# watch.net
KiCad netlist of a schematic drawn in EAGLE
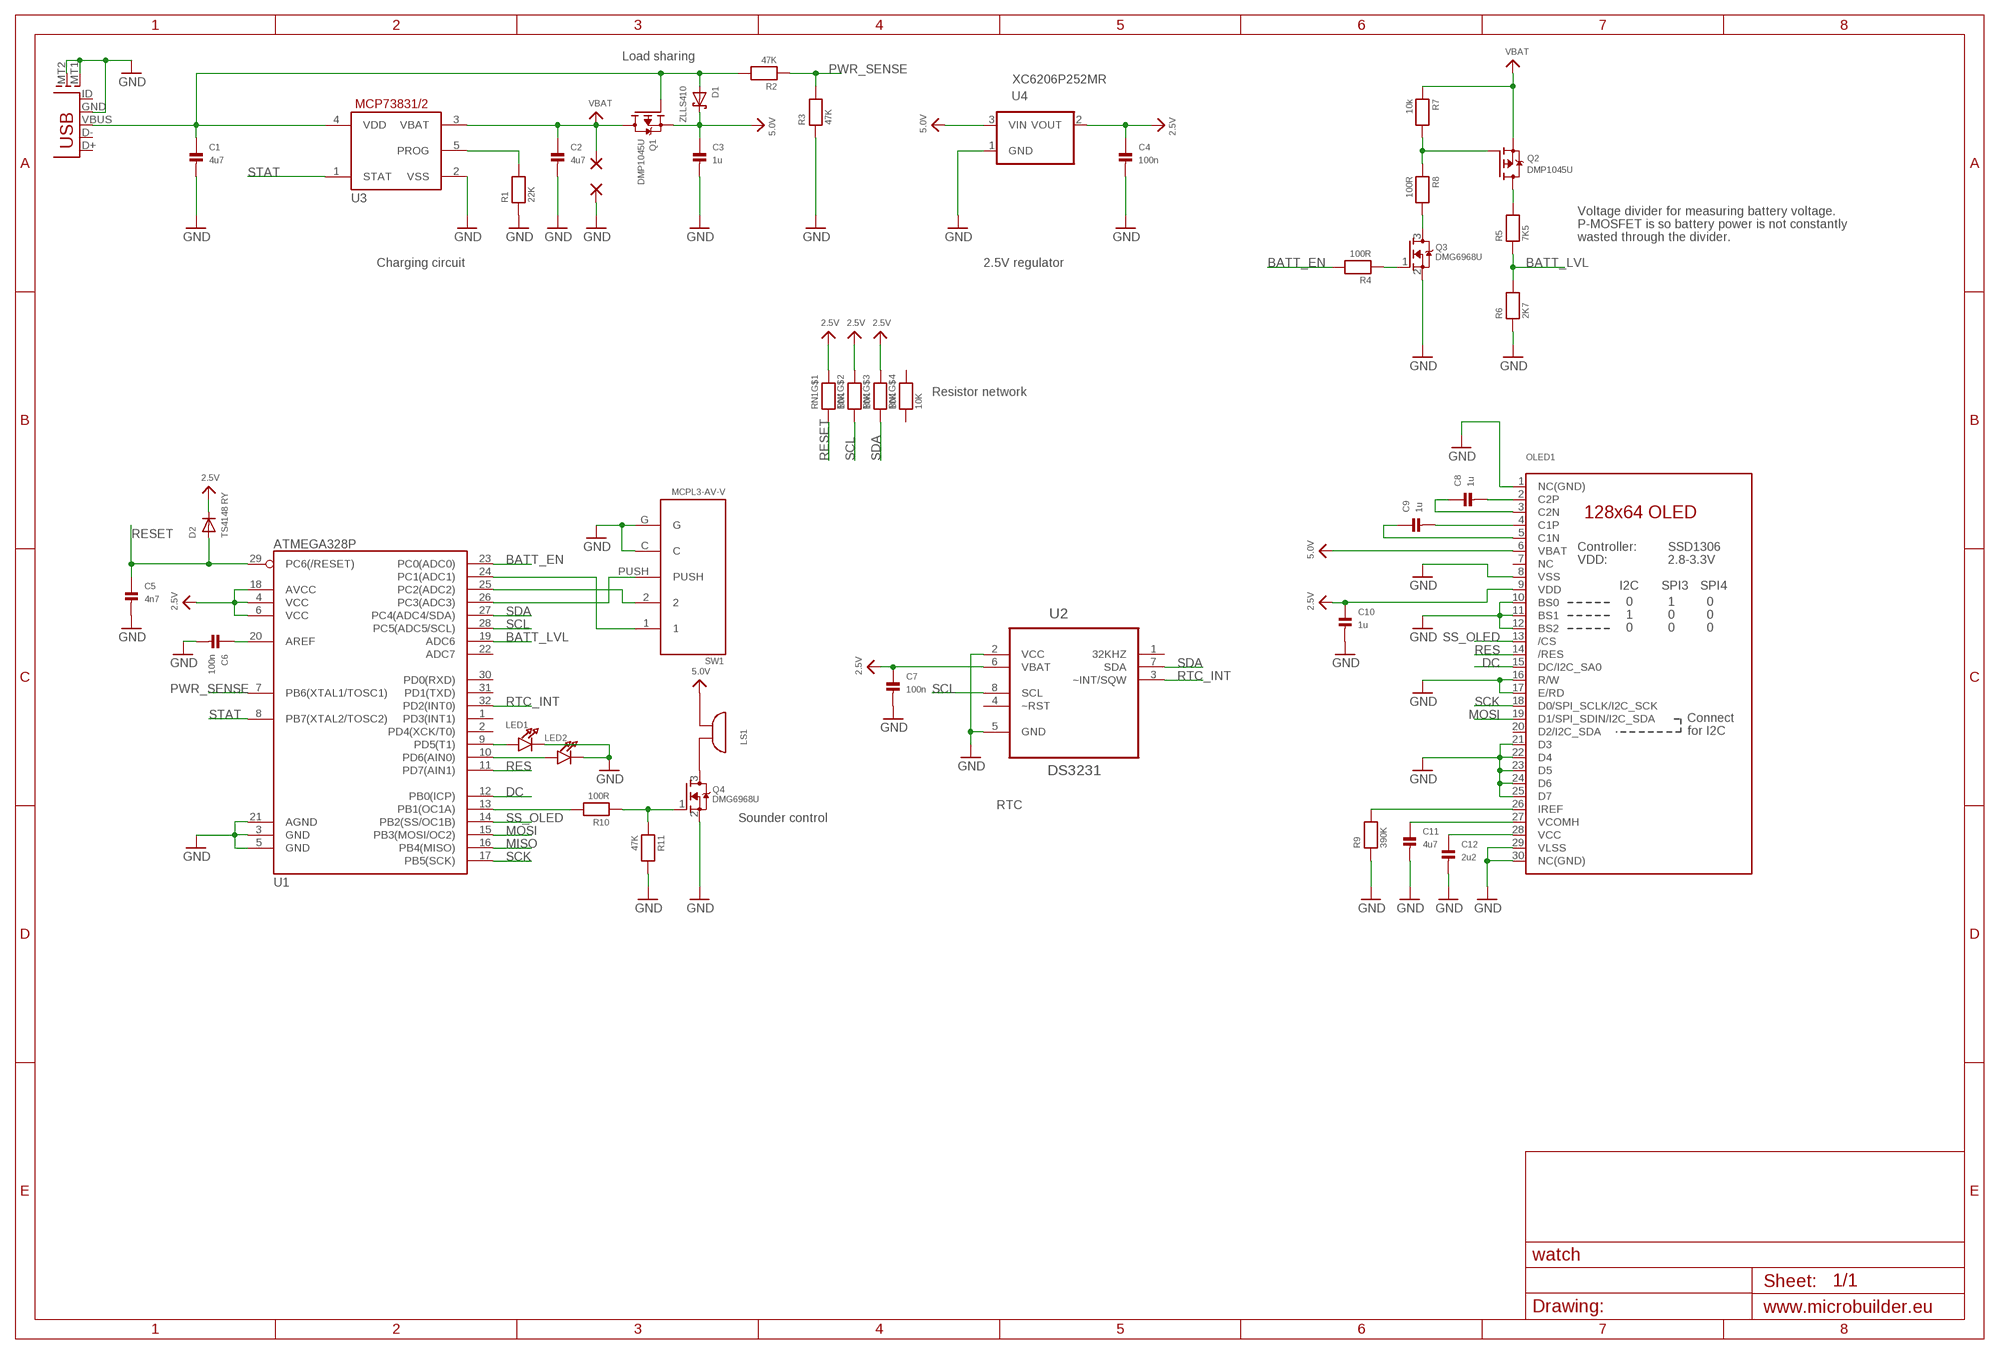
[diagram p0: schematic, sheet 1]

(export (version "E")
  (design (tool "Eeschema 10.0.6"))
  (components
    (comp (ref "C1")
      (value "4u7")
      (footprint "eagle-import:0805")
      (libsource (lib "eagle-import") (part "CAP_CERAMIC0805"))
    )
    (comp (ref "C2")
      (value "4u7")
      (footprint "eagle-import:0805")
      (libsource (lib "eagle-import") (part "CAP_CERAMIC0805"))
    )
    (comp (ref "C3")
      (value "1u")
      (footprint "eagle-import:0805")
      (libsource (lib "eagle-import") (part "CAP_CERAMIC0805"))
    )
    (comp (ref "C4")
      (value "100n")
      (footprint "eagle-import:0805")
      (libsource (lib "eagle-import") (part "CAP_CERAMIC0805"))
    )
    (comp (ref "C5")
      (value "4n7")
      (footprint "eagle-import:0805")
      (libsource (lib "eagle-import") (part "CAP_CERAMIC0805"))
    )
    (comp (ref "C6")
      (value "100n")
      (footprint "eagle-import:0805")
      (libsource (lib "eagle-import") (part "CAP_CERAMIC0805"))
    )
    (comp (ref "C7")
      (value "100n")
      (footprint "eagle-import:0805")
      (libsource (lib "eagle-import") (part "CAP_CERAMIC0805"))
    )
    (comp (ref "C8")
      (value "1u")
      (footprint "eagle-import:0805")
      (libsource (lib "eagle-import") (part "CAP_CERAMIC0805"))
    )
    (comp (ref "C9")
      (value "1u")
      (footprint "eagle-import:0805")
      (libsource (lib "eagle-import") (part "CAP_CERAMIC0805"))
    )
    (comp (ref "C10")
      (value "1u")
      (footprint "eagle-import:0805")
      (libsource (lib "eagle-import") (part "CAP_CERAMIC0805"))
    )
    (comp (ref "C11")
      (value "4u7")
      (footprint "eagle-import:0805")
      (libsource (lib "eagle-import") (part "CAP_CERAMIC0805"))
    )
    (comp (ref "C12")
      (value "2u2")
      (footprint "eagle-import:0805")
      (libsource (lib "eagle-import") (part "CAP_CERAMIC0805"))
    )
    (comp (ref "D1")
      (value "ZLLS410")
      (footprint "eagle-import:SOD-323")
      (libsource (lib "eagle-import") (part "DIODE-SCHOTTKYSOD-323"))
    )
    (comp (ref "D2")
      (value "TS4148 RY")
      (footprint "eagle-import:DIODE0805")
      (libsource (lib "eagle-import") (part "DIODE0805"))
    )
    (comp (ref "LED1")
      (value "LED0805")
      (footprint "eagle-import:CHIPLED_0805")
      (libsource (lib "eagle-import") (part "LED0805"))
    )
    (comp (ref "LED2")
      (value "LED0805")
      (footprint "eagle-import:CHIPLED_0805")
      (libsource (lib "eagle-import") (part "LED0805"))
    )
    (comp (ref "LS1")
      (value "ABMT-801-RC")
      (footprint "eagle-import:PIEZO")
      (libsource (lib "eagle-import") (part "ABMT-801-RC"))
    )
    (comp (ref "OLED1")
      (value "DISP_OLED_UG-2864HSWEG01_NOOUTLINE")
      (footprint "eagle-import:UG-2864HSWEG01_1.3_WRAPAROUND")
      (libsource (lib "eagle-import") (part "DISP_OLED_UG-2864HSWEG01_NOOUTLINE"))
    )
    (comp (ref "PAD1")
      (value "SMD2")
      (footprint "eagle-import:SMD1,27-2,54")
      (libsource (lib "eagle-import") (part "SMD2"))
    )
    (comp (ref "PAD2")
      (value "SMD2")
      (footprint "eagle-import:SMD1,27-2,54")
      (libsource (lib "eagle-import") (part "SMD2"))
    )
    (comp (ref "Q1")
      (value "DMP1045U")
      (footprint "eagle-import:SOT23-WIDE")
      (libsource (lib "eagle-import") (part "MOSFET-PWIDE"))
    )
    (comp (ref "Q2")
      (value "DMP1045U")
      (footprint "eagle-import:SOT23-WIDE")
      (libsource (lib "eagle-import") (part "MOSFET-PWIDE"))
    )
    (comp (ref "Q3")
      (value "DMG6968U")
      (footprint "eagle-import:SOT23-WIDE")
      (libsource (lib "eagle-import") (part "MOSFET-NWIDE"))
    )
    (comp (ref "Q4")
      (value "DMG6968U")
      (footprint "eagle-import:SOT23-WIDE")
      (libsource (lib "eagle-import") (part "MOSFET-NWIDE"))
    )
    (comp (ref "R1")
      (value "22K")
      (footprint "eagle-import:0805")
      (libsource (lib "eagle-import") (part "RESISTOR0805"))
    )
    (comp (ref "R2")
      (value "47K")
      (footprint "eagle-import:0805_NOTHERMALS")
      (libsource (lib "eagle-import") (part "RESISTOR0805_NOTHERMALS"))
    )
    (comp (ref "R3")
      (value "47K")
      (footprint "eagle-import:0805_NOTHERMALS")
      (libsource (lib "eagle-import") (part "RESISTOR0805_NOTHERMALS"))
    )
    (comp (ref "R4")
      (value "100R")
      (footprint "eagle-import:0805")
      (libsource (lib "eagle-import") (part "RESISTOR0805"))
    )
    (comp (ref "R5")
      (value "7K5")
      (footprint "eagle-import:0805")
      (libsource (lib "eagle-import") (part "RESISTOR0805"))
    )
    (comp (ref "R6")
      (value "2K7")
      (footprint "eagle-import:0805")
      (libsource (lib "eagle-import") (part "RESISTOR0805"))
    )
    (comp (ref "R7")
      (value "10k")
      (footprint "eagle-import:0805")
      (libsource (lib "eagle-import") (part "RESISTOR0805"))
    )
    (comp (ref "R8")
      (value "100R")
      (footprint "eagle-import:0805")
      (libsource (lib "eagle-import") (part "RESISTOR0805"))
    )
    (comp (ref "R9")
      (value "390K")
      (footprint "eagle-import:0805")
      (libsource (lib "eagle-import") (part "RESISTOR0805"))
    )
    (comp (ref "R10")
      (value "100R")
      (footprint "eagle-import:0805")
      (libsource (lib "eagle-import") (part "RESISTOR0805"))
    )
    (comp (ref "R11")
      (value "47K")
      (footprint "eagle-import:0805")
      (libsource (lib "eagle-import") (part "RESISTOR0805"))
    )
    (comp (ref "RN1")
      (value "10K")
      (footprint "eagle-import:RESPACK_4X0603")
      (libsource (lib "eagle-import") (part "RESISTOR_4PACK"))
    )
    (comp (ref "SW1")
      (value "MCPL3-AV-V")
      (footprint "eagle-import:MCPL3-AC-V")
      (libsource (lib "eagle-import") (part "MCPL3-AV-V"))
    )
    (comp (ref "U1")
      (value "ATMEGA328P")
      (footprint "eagle-import:TQFP32-08")
      (libsource (lib "eagle-import") (part "ATMEGA328_SMT"))
    )
    (comp (ref "U2")
      (value "DS3231")
      (footprint "eagle-import:SOIC8_150MIL")
      (libsource (lib "eagle-import") (part "DS3231MZ+"))
    )
    (comp (ref "U3")
      (value "MCP73832T-2ACI/OT")
      (footprint "eagle-import:SOT23-5L")
      (libsource (lib "eagle-import") (part "MCP73831/OT"))
    )
    (comp (ref "U4")
      (value "XC6206P252MR")
      (footprint "eagle-import:SOT-23")
      (libsource (lib "eagle-import") (part "MCP1700T-2502E/TTWIDE_PAD"))
    )
    (comp (ref "USB1")
      (value "USB-MICROBLARGEPAD")
      (footprint "eagle-import:USB-MICROB_LARGEPAD")
      (libsource (lib "eagle-import") (part "USB-MICROBLARGEPAD"))
    )
  )
  (nets
    (net (code "1") (name "/BATT_EN") (class "Default")
      (node (ref "R4") (pin "2") (pinfunction "2_2") (pintype "passive"))
      (node (ref "U1") (pin "23") (pinfunction "PC0(ADC0)_23") (pintype "bidirectional"))
    )
    (net (code "2") (name "/BATT_LVL") (class "Default")
      (node (ref "R5") (pin "1") (pinfunction "1_1") (pintype "passive"))
      (node (ref "R6") (pin "2") (pinfunction "2_2") (pintype "passive"))
      (node (ref "U1") (pin "19") (pinfunction "ADC6_19") (pintype "bidirectional"))
    )
    (net (code "3") (name "/DC") (class "Default")
      (node (ref "OLED1") (pin "15") (pinfunction "DC/I2C_SA0_15") (pintype "input"))
      (node (ref "U1") (pin "12") (pinfunction "PB0(ICP)_12") (pintype "bidirectional"))
    )
    (net (code "4") (name "/MISO") (class "Default")
      (node (ref "U1") (pin "16") (pinfunction "PB4(MISO)_16") (pintype "bidirectional"))
    )
    (net (code "5") (name "/MOSI") (class "Default")
      (node (ref "OLED1") (pin "19") (pinfunction "D1/SPI_SDIN/I2C_SDA_19") (pintype "bidirectional"))
      (node (ref "U1") (pin "15") (pinfunction "PB3(MOSI/OC2)_15") (pintype "bidirectional"))
    )
    (net (code "6") (name "/PWR_SENSE") (class "Default")
      (node (ref "R2") (pin "1") (pinfunction "1_1") (pintype "passive"))
      (node (ref "R3") (pin "2") (pinfunction "2_2") (pintype "passive"))
      (node (ref "U1") (pin "7") (pinfunction "PB6(XTAL1/TOSC1)_7") (pintype "bidirectional"))
    )
    (net (code "7") (name "/RES") (class "Default")
      (node (ref "OLED1") (pin "14") (pinfunction "/RES_14") (pintype "input"))
      (node (ref "U1") (pin "11") (pinfunction "PD7(AIN1)_11") (pintype "bidirectional"))
    )
    (net (code "8") (name "/RESET") (class "Default")
      (node (ref "C5") (pin "1") (pinfunction "P$1_1") (pintype "passive"))
      (node (ref "D2") (pin "1") (pinfunction "A_1") (pintype "passive"))
      (node (ref "RN1") (pin "1") (pinfunction "1_1") (pintype "passive"))
      (node (ref "U1") (pin "29") (pinfunction "PC6(/RESET)_29") (pintype "bidirectional"))
    )
    (net (code "9") (name "/RTC_INT") (class "Default")
      (node (ref "U1") (pin "32") (pinfunction "PD2(INT0)_32") (pintype "bidirectional"))
      (node (ref "U2") (pin "3") (pinfunction "~{INT/SQW}_3") (pintype "output"))
    )
    (net (code "10") (name "/SCK") (class "Default")
      (node (ref "OLED1") (pin "18") (pinfunction "D0/SPI_SCLK/I2C_SCK_18") (pintype "bidirectional"))
      (node (ref "U1") (pin "17") (pinfunction "PB5(SCK)_17") (pintype "bidirectional"))
    )
    (net (code "11") (name "/SCL") (class "Default")
      (node (ref "RN1") (pin "2") (pinfunction "1_2") (pintype "passive"))
      (node (ref "U1") (pin "28") (pinfunction "PC5(ADC5/SCL)_28") (pintype "bidirectional"))
      (node (ref "U2") (pin "8") (pinfunction "SCL_8") (pintype "input"))
    )
    (net (code "12") (name "/SDA") (class "Default")
      (node (ref "RN1") (pin "3") (pinfunction "1_3") (pintype "passive"))
      (node (ref "U1") (pin "27") (pinfunction "PC4(ADC4/SDA)_27") (pintype "bidirectional"))
      (node (ref "U2") (pin "7") (pinfunction "SDA_7") (pintype "bidirectional"))
    )
    (net (code "13") (name "/SS_OLED") (class "Default")
      (node (ref "OLED1") (pin "13") (pinfunction "/CS_13") (pintype "input"))
      (node (ref "U1") (pin "14") (pinfunction "PB2(SS/OC1B)_14") (pintype "bidirectional"))
    )
    (net (code "14") (name "/STAT") (class "Default")
      (node (ref "U1") (pin "8") (pinfunction "PB7(XTAL2/TOSC2)_8") (pintype "bidirectional"))
      (node (ref "U3") (pin "1") (pinfunction "STAT_1") (pintype "output"))
    )
    (net (code "15") (name "2.5V") (class "Default")
      (node (ref "C10") (pin "1") (pinfunction "P$1_1") (pintype "passive"))
      (node (ref "C4") (pin "1") (pinfunction "P$1_1") (pintype "passive"))
      (node (ref "C7") (pin "1") (pinfunction "P$1_1") (pintype "passive"))
      (node (ref "D2") (pin "2") (pinfunction "C_2") (pintype "passive"))
      (node (ref "OLED1") (pin "9") (pinfunction "VDD_9") (pintype "power_in"))
      (node (ref "RN1") (pin "6") (pinfunction "2_6") (pintype "passive"))
      (node (ref "RN1") (pin "7") (pinfunction "2_7") (pintype "passive"))
      (node (ref "RN1") (pin "8") (pinfunction "2_8") (pintype "passive"))
      (node (ref "U1") (pin "18") (pinfunction "AVCC_18") (pintype "bidirectional"))
      (node (ref "U1") (pin "4") (pinfunction "VCC_4") (pintype "bidirectional"))
      (node (ref "U1") (pin "6") (pinfunction "VCC_6") (pintype "bidirectional"))
      (node (ref "U2") (pin "6") (pinfunction "VBAT_6") (pintype "power_in"))
      (node (ref "U4") (pin "2") (pinfunction "VOUT_2") (pintype "output"))
    )
    (net (code "16") (name "5.0V") (class "Default")
      (node (ref "C3") (pin "1") (pinfunction "P$1_1") (pintype "passive"))
      (node (ref "D1") (pin "C") (pinfunction "C_C") (pintype "passive"))
      (node (ref "LS1") (pin "1") (pinfunction "VCC_1") (pintype "passive"))
      (node (ref "OLED1") (pin "6") (pinfunction "VBAT_6") (pintype "input"))
      (node (ref "Q1") (pin "2") (pinfunction "S_2") (pintype "passive"))
      (node (ref "U4") (pin "3") (pinfunction "VIN_3") (pintype "power_in"))
    )
    (net (code "17") (name "GND") (class "Default")
      (node (ref "C1") (pin "2") (pinfunction "P$2_2") (pintype "passive"))
      (node (ref "C10") (pin "2") (pinfunction "P$2_2") (pintype "passive"))
      (node (ref "C11") (pin "2") (pinfunction "P$2_2") (pintype "passive"))
      (node (ref "C12") (pin "2") (pinfunction "P$2_2") (pintype "passive"))
      (node (ref "C2") (pin "2") (pinfunction "P$2_2") (pintype "passive"))
      (node (ref "C3") (pin "2") (pinfunction "P$2_2") (pintype "passive"))
      (node (ref "C4") (pin "2") (pinfunction "P$2_2") (pintype "passive"))
      (node (ref "C5") (pin "2") (pinfunction "P$2_2") (pintype "passive"))
      (node (ref "C6") (pin "2") (pinfunction "P$2_2") (pintype "passive"))
      (node (ref "C7") (pin "2") (pinfunction "P$2_2") (pintype "passive"))
      (node (ref "LED1") (pin "C") (pinfunction "C_C") (pintype "passive"))
      (node (ref "LED2") (pin "C") (pinfunction "C_C") (pintype "passive"))
      (node (ref "OLED1") (pin "1") (pinfunction "NC(GND)_1") (pintype "input"))
      (node (ref "OLED1") (pin "10") (pinfunction "BS0_10") (pintype "input"))
      (node (ref "OLED1") (pin "11") (pinfunction "BS1_11") (pintype "input"))
      (node (ref "OLED1") (pin "12") (pinfunction "BS2_12") (pintype "input"))
      (node (ref "OLED1") (pin "16") (pinfunction "R/W_16") (pintype "input"))
      (node (ref "OLED1") (pin "17") (pinfunction "E/RD_17") (pintype "input"))
      (node (ref "OLED1") (pin "21") (pinfunction "D3_21") (pintype "bidirectional"))
      (node (ref "OLED1") (pin "22") (pinfunction "D4_22") (pintype "bidirectional"))
      (node (ref "OLED1") (pin "23") (pinfunction "D5_23") (pintype "bidirectional"))
      (node (ref "OLED1") (pin "24") (pinfunction "D6_24") (pintype "bidirectional"))
      (node (ref "OLED1") (pin "25") (pinfunction "D7_25") (pintype "bidirectional"))
      (node (ref "OLED1") (pin "29") (pinfunction "VLSS_29") (pintype "power_in"))
      (node (ref "OLED1") (pin "30") (pinfunction "NC(GND)_30") (pintype "input"))
      (node (ref "OLED1") (pin "8") (pinfunction "VSS_8") (pintype "power_in"))
      (node (ref "PAD2") (pin "1") (pinfunction "P_1") (pintype "passive"))
      (node (ref "Q3") (pin "2") (pinfunction "S_2") (pintype "bidirectional"))
      (node (ref "Q4") (pin "2") (pinfunction "S_2") (pintype "bidirectional"))
      (node (ref "R1") (pin "1") (pinfunction "1_1") (pintype "passive"))
      (node (ref "R11") (pin "2") (pinfunction "2_2") (pintype "passive"))
      (node (ref "R3") (pin "1") (pinfunction "1_1") (pintype "passive"))
      (node (ref "R6") (pin "1") (pinfunction "1_1") (pintype "passive"))
      (node (ref "R9") (pin "1") (pinfunction "1_1") (pintype "passive"))
      (node (ref "SW1") (pin "C") (pinfunction "C_C") (pintype "bidirectional"))
      (node (ref "SW1") (pin "G") (pinfunction "G_G") (pintype "bidirectional"))
      (node (ref "U1") (pin "21") (pinfunction "AGND_21") (pintype "bidirectional"))
      (node (ref "U1") (pin "3") (pinfunction "GND_3") (pintype "bidirectional"))
      (node (ref "U1") (pin "5") (pinfunction "GND_5") (pintype "bidirectional"))
      (node (ref "U2") (pin "2") (pinfunction "VCC_2") (pintype "power_in"))
      (node (ref "U2") (pin "5") (pinfunction "GND_5") (pintype "passive"))
      (node (ref "U3") (pin "2") (pinfunction "VSS_2") (pintype "power_in"))
      (node (ref "U4") (pin "1") (pinfunction "GND_1") (pintype "passive"))
      (node (ref "USB1") (pin "GND") (pinfunction "GND_GND") (pintype "bidirectional"))
      (node (ref "USB1") (pin "MT1") (pinfunction "SHEILD1_MT1") (pintype "bidirectional"))
      (node (ref "USB1") (pin "MT2") (pinfunction "SHEILD2_MT2") (pintype "bidirectional"))
    )
    (net (code "18") (name "Net-(C1-P$1)") (class "Default")
      (node (ref "C1") (pin "1") (pinfunction "P$1_1") (pintype "passive"))
      (node (ref "D1") (pin "A") (pinfunction "A_A") (pintype "passive"))
      (node (ref "Q1") (pin "1") (pinfunction "G_1") (pintype "passive"))
      (node (ref "R2") (pin "2") (pinfunction "2_2") (pintype "passive"))
      (node (ref "U3") (pin "4") (pinfunction "VDD_4") (pintype "power_in"))
      (node (ref "USB1") (pin "VBUS") (pinfunction "VBUS_VBUS") (pintype "bidirectional"))
    )
    (net (code "19") (name "Net-(C6-P$1)") (class "Default")
      (node (ref "C6") (pin "1") (pinfunction "P$1_1") (pintype "passive"))
      (node (ref "U1") (pin "20") (pinfunction "AREF_20") (pintype "bidirectional"))
    )
    (net (code "20") (name "Net-(C8-P$1)") (class "Default")
      (node (ref "C8") (pin "1") (pinfunction "P$1_1") (pintype "passive"))
      (node (ref "OLED1") (pin "3") (pinfunction "C2N_3") (pintype "input"))
    )
    (net (code "21") (name "Net-(C8-P$2)") (class "Default")
      (node (ref "C8") (pin "2") (pinfunction "P$2_2") (pintype "passive"))
      (node (ref "OLED1") (pin "2") (pinfunction "C2P_2") (pintype "input"))
    )
    (net (code "22") (name "Net-(C9-P$1)") (class "Default")
      (node (ref "C9") (pin "1") (pinfunction "P$1_1") (pintype "passive"))
      (node (ref "OLED1") (pin "5") (pinfunction "C1N_5") (pintype "input"))
    )
    (net (code "23") (name "Net-(C9-P$2)") (class "Default")
      (node (ref "C9") (pin "2") (pinfunction "P$2_2") (pintype "passive"))
      (node (ref "OLED1") (pin "4") (pinfunction "C1P_4") (pintype "input"))
    )
    (net (code "24") (name "Net-(C11-P$1)") (class "Default")
      (node (ref "C11") (pin "1") (pinfunction "P$1_1") (pintype "passive"))
      (node (ref "OLED1") (pin "27") (pinfunction "VCOMH_27") (pintype "output"))
    )
    (net (code "25") (name "Net-(C12-P$1)") (class "Default")
      (node (ref "C12") (pin "1") (pinfunction "P$1_1") (pintype "passive"))
      (node (ref "OLED1") (pin "28") (pinfunction "VCC_28") (pintype "power_in"))
    )
    (net (code "26") (name "Net-(LS1-GND)") (class "Default")
      (node (ref "LS1") (pin "2") (pinfunction "GND_2") (pintype "passive"))
      (node (ref "Q4") (pin "3") (pinfunction "D_3") (pintype "bidirectional"))
    )
    (net (code "27") (name "Net-(OLED1-IREF)") (class "Default")
      (node (ref "OLED1") (pin "26") (pinfunction "IREF_26") (pintype "input"))
      (node (ref "R9") (pin "2") (pinfunction "2_2") (pintype "passive"))
    )
    (net (code "28") (name "Net-(Q2-D)") (class "Default")
      (node (ref "Q2") (pin "3") (pinfunction "D_3") (pintype "passive"))
      (node (ref "R5") (pin "2") (pinfunction "2_2") (pintype "passive"))
    )
    (net (code "29") (name "Net-(Q2-G)") (class "Default")
      (node (ref "Q2") (pin "1") (pinfunction "G_1") (pintype "passive"))
      (node (ref "R7") (pin "2") (pinfunction "2_2") (pintype "passive"))
      (node (ref "R8") (pin "1") (pinfunction "1_1") (pintype "passive"))
    )
    (net (code "30") (name "Net-(Q3-D)") (class "Default")
      (node (ref "Q3") (pin "3") (pinfunction "D_3") (pintype "bidirectional"))
      (node (ref "R8") (pin "2") (pinfunction "2_2") (pintype "passive"))
    )
    (net (code "31") (name "Net-(Q3-G)") (class "Default")
      (node (ref "Q3") (pin "1") (pinfunction "G_1") (pintype "bidirectional"))
      (node (ref "R4") (pin "1") (pinfunction "1_1") (pintype "passive"))
    )
    (net (code "32") (name "Net-(Q4-G)") (class "Default")
      (node (ref "Q4") (pin "1") (pinfunction "G_1") (pintype "bidirectional"))
      (node (ref "R10") (pin "1") (pinfunction "1_1") (pintype "passive"))
      (node (ref "R11") (pin "1") (pinfunction "1_1") (pintype "passive"))
    )
    (net (code "33") (name "Net-(U1-PB1(OC1A))") (class "Default")
      (node (ref "R10") (pin "2") (pinfunction "2_2") (pintype "passive"))
      (node (ref "U1") (pin "13") (pinfunction "PB1(OC1A)_13") (pintype "bidirectional"))
    )
    (net (code "34") (name "Net-(U1-PC1(ADC1))") (class "Default")
      (node (ref "SW1") (pin "1") (pinfunction "1_1") (pintype "bidirectional"))
      (node (ref "U1") (pin "24") (pinfunction "PC1(ADC1)_24") (pintype "bidirectional"))
    )
    (net (code "35") (name "Net-(U1-PC2(ADC2))") (class "Default")
      (node (ref "SW1") (pin "2") (pinfunction "2_2") (pintype "bidirectional"))
      (node (ref "U1") (pin "25") (pinfunction "PC2(ADC2)_25") (pintype "bidirectional"))
    )
    (net (code "36") (name "Net-(U1-PC3(ADC3))") (class "Default")
      (node (ref "SW1") (pin "PUSH") (pinfunction "PUSH_PUSH") (pintype "bidirectional"))
      (node (ref "U1") (pin "26") (pinfunction "PC3(ADC3)_26") (pintype "bidirectional"))
    )
    (net (code "37") (name "Net-(U1-PD5(T1))") (class "Default")
      (node (ref "LED1") (pin "A") (pinfunction "A_A") (pintype "passive"))
      (node (ref "U1") (pin "9") (pinfunction "PD5(T1)_9") (pintype "bidirectional"))
    )
    (net (code "38") (name "Net-(U1-PD6(AIN0))") (class "Default")
      (node (ref "LED2") (pin "A") (pinfunction "A_A") (pintype "passive"))
      (node (ref "U1") (pin "10") (pinfunction "PD6(AIN0)_10") (pintype "bidirectional"))
    )
    (net (code "39") (name "Net-(U3-PROG)") (class "Default")
      (node (ref "R1") (pin "2") (pinfunction "2_2") (pintype "passive"))
      (node (ref "U3") (pin "5") (pinfunction "PROG_5") (pintype "input"))
    )
    (net (code "40") (name "VBAT") (class "Default")
      (node (ref "C2") (pin "1") (pinfunction "P$1_1") (pintype "passive"))
      (node (ref "PAD1") (pin "1") (pinfunction "P_1") (pintype "passive"))
      (node (ref "Q1") (pin "3") (pinfunction "D_3") (pintype "passive"))
      (node (ref "Q2") (pin "2") (pinfunction "S_2") (pintype "passive"))
      (node (ref "R7") (pin "1") (pinfunction "1_1") (pintype "passive"))
      (node (ref "U3") (pin "3") (pinfunction "VBAT_3") (pintype "bidirectional"))
    )
    (net (code "41") (name "unconnected-(OLED1-D2{slash}I2C_SDA-Pad20)") (class "Default")
      (node (ref "OLED1") (pin "20") (pinfunction "D2/I2C_SDA_20") (pintype "bidirectional"))
    )
    (net (code "42") (name "unconnected-(OLED1-NC-Pad7)") (class "Default")
      (node (ref "OLED1") (pin "7") (pinfunction "NC_7") (pintype "no_connect"))
    )
    (net (code "43") (name "unconnected-(RN1D-1-Pad4)") (class "Default")
      (node (ref "RN1") (pin "4") (pinfunction "1_4") (pintype "passive"))
    )
    (net (code "44") (name "unconnected-(RN1D-2-Pad5)") (class "Default")
      (node (ref "RN1") (pin "5") (pinfunction "2_5") (pintype "passive"))
    )
    (net (code "45") (name "unconnected-(U1-ADC7-Pad22)") (class "Default")
      (node (ref "U1") (pin "22") (pinfunction "ADC7_22") (pintype "bidirectional"))
    )
    (net (code "46") (name "unconnected-(U1-PD0(RXD)-Pad30)") (class "Default")
      (node (ref "U1") (pin "30") (pinfunction "PD0(RXD)_30") (pintype "bidirectional"))
    )
    (net (code "47") (name "unconnected-(U1-PD1(TXD)-Pad31)") (class "Default")
      (node (ref "U1") (pin "31") (pinfunction "PD1(TXD)_31") (pintype "bidirectional"))
    )
    (net (code "48") (name "unconnected-(U1-PD3(INT1)-Pad1)") (class "Default")
      (node (ref "U1") (pin "1") (pinfunction "PD3(INT1)_1") (pintype "bidirectional"))
    )
    (net (code "49") (name "unconnected-(U1-PD4(XCK{slash}T0)-Pad2)") (class "Default")
      (node (ref "U1") (pin "2") (pinfunction "PD4(XCK/T0)_2") (pintype "bidirectional"))
    )
    (net (code "50") (name "unconnected-(U2-32KHZ-Pad1)") (class "Default")
      (node (ref "U2") (pin "1") (pinfunction "32KHZ_1") (pintype "output"))
    )
    (net (code "51") (name "unconnected-(U2-~{RST}-Pad4)") (class "Default")
      (node (ref "U2") (pin "4") (pinfunction "~{RST}_4") (pintype "bidirectional"))
    )
    (net (code "52") (name "unconnected-(USB1-PadD+)") (class "Default")
      (node (ref "USB1") (pin "D+") (pinfunction "D+_D+") (pintype "bidirectional"))
    )
    (net (code "53") (name "unconnected-(USB1-PadD-)") (class "Default")
      (node (ref "USB1") (pin "D-") (pinfunction "D-_D-") (pintype "bidirectional"))
    )
    (net (code "54") (name "unconnected-(USB1-PadID)") (class "Default")
      (node (ref "USB1") (pin "ID") (pinfunction "ID_ID") (pintype "bidirectional"))
    )
  )
)
